# rgbamp.net
KiCad netlist of a schematic drawn in EAGLE
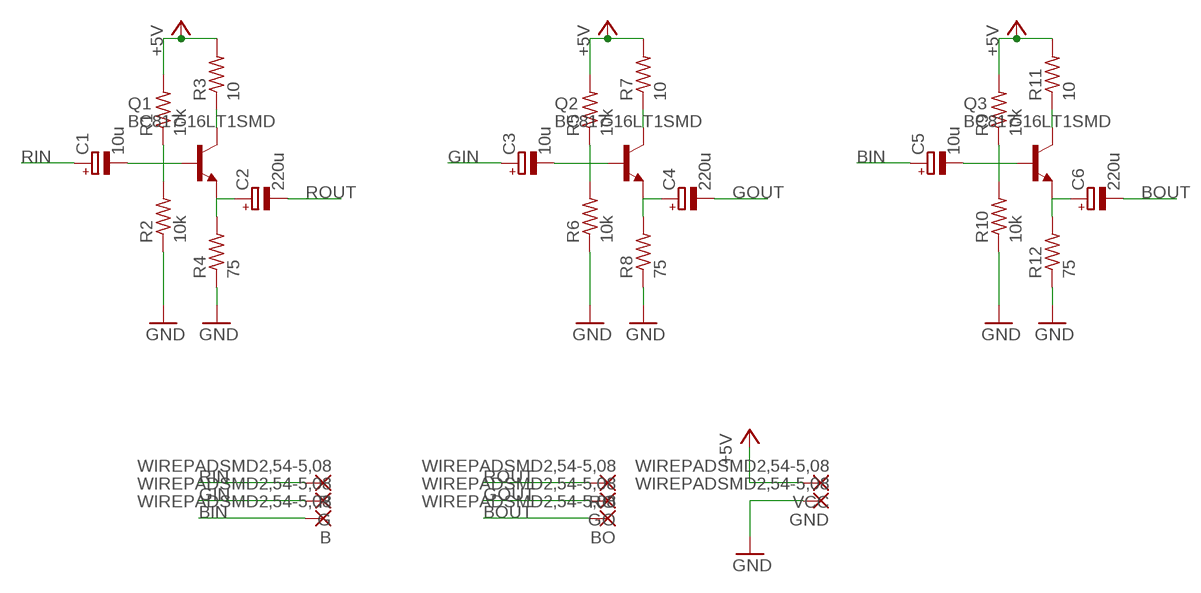
[diagram p0: schematic, sheet 1]

(export (version "E")
  (design (tool "Eeschema 10.0.6"))
  (components
    (comp (ref "B")
      (value "WIREPADSMD2,54-5,08")
      (footprint "eagle-import:SMD2,54-5,08")
      (libsource (lib "eagle-import") (part "WIREPADSMD2,54-5,08"))
    )
    (comp (ref "BO")
      (value "WIREPADSMD2,54-5,08")
      (footprint "eagle-import:SMD2,54-5,08")
      (libsource (lib "eagle-import") (part "WIREPADSMD2,54-5,08"))
    )
    (comp (ref "C1")
      (value "10u")
      (footprint "eagle-import:150CLZ-0810")
      (libsource (lib "eagle-import") (part "CPOL-EU150CLZ-0810"))
    )
    (comp (ref "C2")
      (value "220u")
      (footprint "eagle-import:150CLZ-0810")
      (libsource (lib "eagle-import") (part "CPOL-EU150CLZ-0810"))
    )
    (comp (ref "C3")
      (value "10u")
      (footprint "eagle-import:150CLZ-0810")
      (libsource (lib "eagle-import") (part "CPOL-EU150CLZ-0810"))
    )
    (comp (ref "C4")
      (value "220u")
      (footprint "eagle-import:PANASONIC_D")
      (libsource (lib "eagle-import") (part "CPOL-EUD"))
    )
    (comp (ref "C5")
      (value "10u")
      (footprint "eagle-import:150CLZ-0810")
      (libsource (lib "eagle-import") (part "CPOL-EU150CLZ-0810"))
    )
    (comp (ref "C6")
      (value "220u")
      (footprint "eagle-import:PANASONIC_D")
      (libsource (lib "eagle-import") (part "CPOL-EUD"))
    )
    (comp (ref "G")
      (value "WIREPADSMD2,54-5,08")
      (footprint "eagle-import:SMD2,54-5,08")
      (libsource (lib "eagle-import") (part "WIREPADSMD2,54-5,08"))
    )
    (comp (ref "GND")
      (value "WIREPADSMD2,54-5,08")
      (footprint "eagle-import:SMD2,54-5,08")
      (libsource (lib "eagle-import") (part "WIREPADSMD2,54-5,08"))
    )
    (comp (ref "GO")
      (value "WIREPADSMD2,54-5,08")
      (footprint "eagle-import:SMD2,54-5,08")
      (libsource (lib "eagle-import") (part "WIREPADSMD2,54-5,08"))
    )
    (comp (ref "Q1")
      (value "BC817-16LT1SMD")
      (footprint "eagle-import:SOT23-BEC")
      (libsource (lib "eagle-import") (part "BC817SMD-16LT1"))
    )
    (comp (ref "Q2")
      (value "BC817-16LT1SMD")
      (footprint "eagle-import:SOT23-BEC")
      (libsource (lib "eagle-import") (part "BC817SMD-16LT1"))
    )
    (comp (ref "Q3")
      (value "BC817-16LT1SMD")
      (footprint "eagle-import:SOT23-BEC")
      (libsource (lib "eagle-import") (part "BC817SMD-16LT1"))
    )
    (comp (ref "R")
      (value "WIREPADSMD2,54-5,08")
      (footprint "eagle-import:SMD2,54-5,08")
      (libsource (lib "eagle-import") (part "WIREPADSMD2,54-5,08"))
    )
    (comp (ref "R1")
      (value "10k")
      (footprint "eagle-import:M1206")
      (libsource (lib "eagle-import") (part "R-US_M1206"))
    )
    (comp (ref "R2")
      (value "10k")
      (footprint "eagle-import:M1206")
      (libsource (lib "eagle-import") (part "R-US_M1206"))
    )
    (comp (ref "R3")
      (value "10")
      (footprint "eagle-import:M1206")
      (libsource (lib "eagle-import") (part "R-US_M1206"))
    )
    (comp (ref "R4")
      (value "75")
      (footprint "eagle-import:M1206")
      (libsource (lib "eagle-import") (part "R-US_M1206"))
    )
    (comp (ref "R5")
      (value "10k")
      (footprint "eagle-import:M1206")
      (libsource (lib "eagle-import") (part "R-US_M1206"))
    )
    (comp (ref "R6")
      (value "10k")
      (footprint "eagle-import:M1206")
      (libsource (lib "eagle-import") (part "R-US_M1206"))
    )
    (comp (ref "R7")
      (value "10")
      (footprint "eagle-import:M1206")
      (libsource (lib "eagle-import") (part "R-US_M1206"))
    )
    (comp (ref "R8")
      (value "75")
      (footprint "eagle-import:M1206")
      (libsource (lib "eagle-import") (part "R-US_M1206"))
    )
    (comp (ref "R9")
      (value "10k")
      (footprint "eagle-import:M1206")
      (libsource (lib "eagle-import") (part "R-US_M1206"))
    )
    (comp (ref "R10")
      (value "10k")
      (footprint "eagle-import:M1206")
      (libsource (lib "eagle-import") (part "R-US_M1206"))
    )
    (comp (ref "R11")
      (value "10")
      (footprint "eagle-import:M1206")
      (libsource (lib "eagle-import") (part "R-US_M1206"))
    )
    (comp (ref "R12")
      (value "75")
      (footprint "eagle-import:M1206")
      (libsource (lib "eagle-import") (part "R-US_M1206"))
    )
    (comp (ref "RO")
      (value "WIREPADSMD2,54-5,08")
      (footprint "eagle-import:SMD2,54-5,08")
      (libsource (lib "eagle-import") (part "WIREPADSMD2,54-5,08"))
    )
    (comp (ref "VCC")
      (value "WIREPADSMD2,54-5,08")
      (footprint "eagle-import:SMD2,54-5,08")
      (libsource (lib "eagle-import") (part "WIREPADSMD2,54-5,08"))
    )
  )
  (nets
    (net (code "1") (name "+5V") (class "Default")
      (node (ref "R1") (pin "2") (pinfunction "2_2") (pintype "passive"))
      (node (ref "R11") (pin "2") (pinfunction "2_2") (pintype "passive"))
      (node (ref "R3") (pin "2") (pinfunction "2_2") (pintype "passive"))
      (node (ref "R5") (pin "2") (pinfunction "2_2") (pintype "passive"))
      (node (ref "R7") (pin "2") (pinfunction "2_2") (pintype "passive"))
      (node (ref "R9") (pin "2") (pinfunction "2_2") (pintype "passive"))
      (node (ref "VCC") (pin "1") (pinfunction "P_1") (pintype "passive"))
    )
    (net (code "2") (name "/BIN") (class "Default")
      (node (ref "B") (pin "1") (pinfunction "P_1") (pintype "passive"))
      (node (ref "C5") (pin "+") (pinfunction "+_+") (pintype "passive"))
    )
    (net (code "3") (name "/BOUT") (class "Default")
      (node (ref "BO") (pin "1") (pinfunction "P_1") (pintype "passive"))
      (node (ref "C6") (pin "-") (pinfunction "-_-") (pintype "passive"))
    )
    (net (code "4") (name "/GIN") (class "Default")
      (node (ref "C3") (pin "+") (pinfunction "+_+") (pintype "passive"))
      (node (ref "G") (pin "1") (pinfunction "P_1") (pintype "passive"))
    )
    (net (code "5") (name "/GOUT") (class "Default")
      (node (ref "C4") (pin "-") (pinfunction "-_-") (pintype "passive"))
      (node (ref "GO") (pin "1") (pinfunction "P_1") (pintype "passive"))
    )
    (net (code "6") (name "/RIN") (class "Default")
      (node (ref "C1") (pin "+") (pinfunction "+_+") (pintype "passive"))
      (node (ref "R") (pin "1") (pinfunction "P_1") (pintype "passive"))
    )
    (net (code "7") (name "/ROUT") (class "Default")
      (node (ref "C2") (pin "-") (pinfunction "-_-") (pintype "passive"))
      (node (ref "RO") (pin "1") (pinfunction "P_1") (pintype "passive"))
    )
    (net (code "8") (name "GND") (class "Default")
      (node (ref "GND") (pin "1") (pinfunction "P_1") (pintype "passive"))
      (node (ref "R10") (pin "1") (pinfunction "1_1") (pintype "passive"))
      (node (ref "R12") (pin "1") (pinfunction "1_1") (pintype "passive"))
      (node (ref "R2") (pin "1") (pinfunction "1_1") (pintype "passive"))
      (node (ref "R4") (pin "1") (pinfunction "1_1") (pintype "passive"))
      (node (ref "R6") (pin "1") (pinfunction "1_1") (pintype "passive"))
      (node (ref "R8") (pin "1") (pinfunction "1_1") (pintype "passive"))
    )
    (net (code "9") (name "Net-(C1-Pad-)") (class "Default")
      (node (ref "C1") (pin "-") (pinfunction "-_-") (pintype "passive"))
      (node (ref "Q1") (pin "B") (pinfunction "B_B") (pintype "passive"))
      (node (ref "R1") (pin "1") (pinfunction "1_1") (pintype "passive"))
      (node (ref "R2") (pin "2") (pinfunction "2_2") (pintype "passive"))
    )
    (net (code "10") (name "Net-(C2-Pad+)") (class "Default")
      (node (ref "C2") (pin "+") (pinfunction "+_+") (pintype "passive"))
      (node (ref "Q1") (pin "E") (pinfunction "E_E") (pintype "passive"))
      (node (ref "R4") (pin "2") (pinfunction "2_2") (pintype "passive"))
    )
    (net (code "11") (name "Net-(C3-Pad-)") (class "Default")
      (node (ref "C3") (pin "-") (pinfunction "-_-") (pintype "passive"))
      (node (ref "Q2") (pin "B") (pinfunction "B_B") (pintype "passive"))
      (node (ref "R5") (pin "1") (pinfunction "1_1") (pintype "passive"))
      (node (ref "R6") (pin "2") (pinfunction "2_2") (pintype "passive"))
    )
    (net (code "12") (name "Net-(C4-Pad+)") (class "Default")
      (node (ref "C4") (pin "+") (pinfunction "+_+") (pintype "passive"))
      (node (ref "Q2") (pin "E") (pinfunction "E_E") (pintype "passive"))
      (node (ref "R8") (pin "2") (pinfunction "2_2") (pintype "passive"))
    )
    (net (code "13") (name "Net-(C5-Pad-)") (class "Default")
      (node (ref "C5") (pin "-") (pinfunction "-_-") (pintype "passive"))
      (node (ref "Q3") (pin "B") (pinfunction "B_B") (pintype "passive"))
      (node (ref "R10") (pin "2") (pinfunction "2_2") (pintype "passive"))
      (node (ref "R9") (pin "1") (pinfunction "1_1") (pintype "passive"))
    )
    (net (code "14") (name "Net-(C6-Pad+)") (class "Default")
      (node (ref "C6") (pin "+") (pinfunction "+_+") (pintype "passive"))
      (node (ref "Q3") (pin "E") (pinfunction "E_E") (pintype "passive"))
      (node (ref "R12") (pin "2") (pinfunction "2_2") (pintype "passive"))
    )
    (net (code "15") (name "Net-(Q1-PadC)") (class "Default")
      (node (ref "Q1") (pin "C") (pinfunction "C_C") (pintype "passive"))
      (node (ref "R3") (pin "1") (pinfunction "1_1") (pintype "passive"))
    )
    (net (code "16") (name "Net-(Q2-PadC)") (class "Default")
      (node (ref "Q2") (pin "C") (pinfunction "C_C") (pintype "passive"))
      (node (ref "R7") (pin "1") (pinfunction "1_1") (pintype "passive"))
    )
    (net (code "17") (name "Net-(Q3-PadC)") (class "Default")
      (node (ref "Q3") (pin "C") (pinfunction "C_C") (pintype "passive"))
      (node (ref "R11") (pin "1") (pinfunction "1_1") (pintype "passive"))
    )
  )
)
